# CircoController.net
KiCad netlist of a schematic drawn in EAGLE
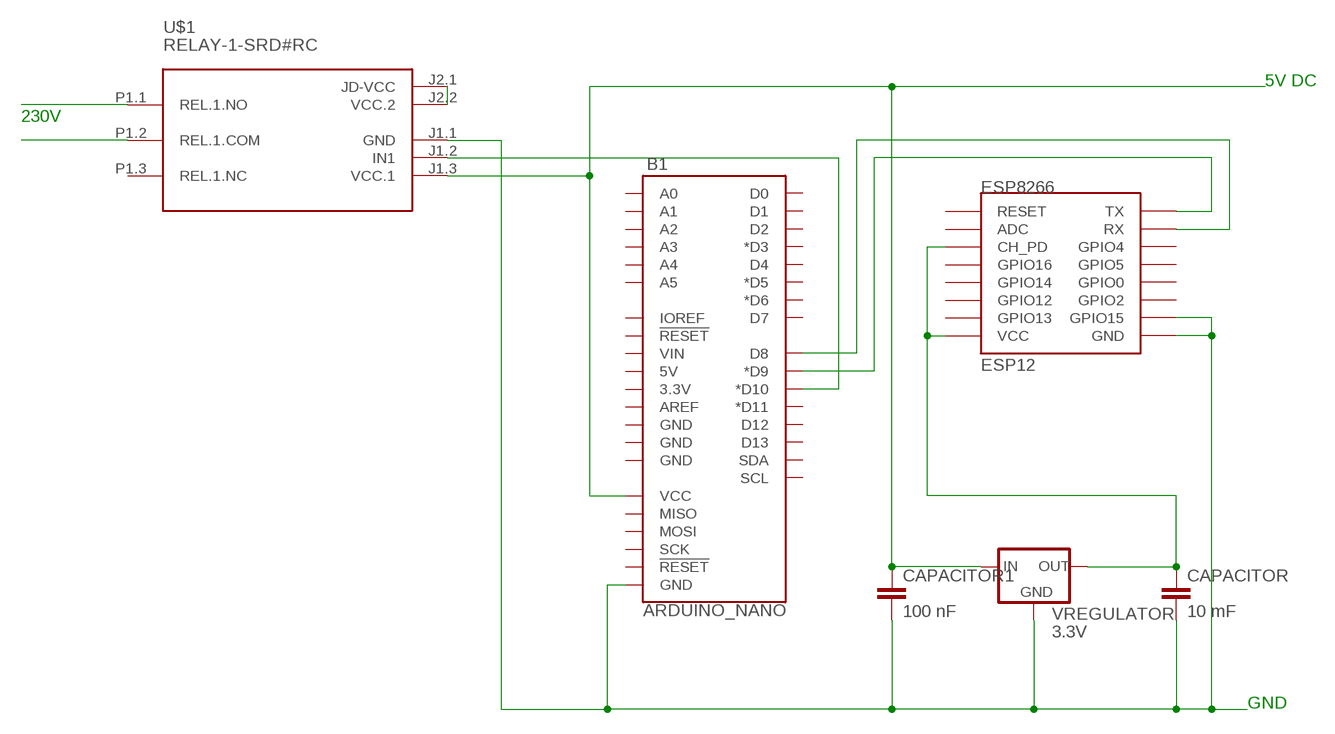
[diagram p0: schematic, sheet 1]

(export (version "E")
  (design (tool "Eeschema 10.0.6"))
  (components
    (comp (ref "B1")
      (value "ARDUINO_NANO")
      (footprint "eagle-import:ARDUINO_R3")
      (libsource (lib "eagle-import") (part "ARDUINO_UNO_R3"))
    )
    (comp (ref "CAPACITOR")
      (value "10 mF")
      (footprint "eagle-import:RESC0201_L")
      (libsource (lib "eagle-import") (part "CAPACITOR_0201_L"))
    )
    (comp (ref "CAPACITOR1")
      (value "100 nF")
      (footprint "eagle-import:RESC0201_L")
      (libsource (lib "eagle-import") (part "CAPACITOR_0201_L"))
    )
    (comp (ref "ESP8266")
      (value "ESP12")
      (footprint "eagle-import:ESP12")
      (libsource (lib "eagle-import") (part "ESP12"))
    )
    (comp (ref "U$1")
      (value "RELAY-1-SRD#RC")
      (footprint "eagle-import:RELAY-1-SRD#RC")
      (libsource (lib "eagle-import") (part "RELAY-1-SRD#RC"))
    )
    (comp (ref "VREGULATOR")
      (value "3.3V")
      (footprint "eagle-import:78LXX")
      (libsource (lib "eagle-import") (part "78LXX"))
    )
  )
  (nets
    (net (code "1") (name "Net-(B1-*D9)") (class "Default")
      (node (ref "B1") (pin "D9") (pinfunction "*D9_D9") (pintype "bidirectional"))
      (node (ref "ESP8266") (pin "TX") (pinfunction "TX_TX") (pintype "bidirectional"))
    )
    (net (code "2") (name "Net-(B1-*D10)") (class "Default")
      (node (ref "B1") (pin "D10") (pinfunction "*D10_D10") (pintype "bidirectional"))
      (node (ref "U$1") (pin "J1.2") (pinfunction "IN1_J1.2") (pintype "bidirectional"))
    )
    (net (code "3") (name "Net-(B1-PadD8)") (class "Default")
      (node (ref "B1") (pin "D8") (pinfunction "D8_D8") (pintype "bidirectional"))
      (node (ref "ESP8266") (pin "RX") (pinfunction "RX_RX") (pintype "bidirectional"))
    )
    (net (code "4") (name "Net-(CAPACITOR-Pad1)") (class "Default")
      (node (ref "CAPACITOR") (pin "1") (pinfunction "1_1") (pintype "passive"))
      (node (ref "ESP8266") (pin "CH_PD") (pinfunction "CH_PD_CH_PD") (pintype "bidirectional"))
      (node (ref "ESP8266") (pin "VCC") (pinfunction "VCC_VCC") (pintype "bidirectional"))
      (node (ref "VREGULATOR") (pin "OUT") (pinfunction "OUT_OUT") (pintype "passive"))
    )
    (net (code "5") (name "Net-(U$1-GND)") (class "Default")
      (node (ref "B1") (pin "GND@1") (pinfunction "GND_GND@1") (pintype "bidirectional"))
      (node (ref "CAPACITOR") (pin "2") (pinfunction "2_2") (pintype "passive"))
      (node (ref "CAPACITOR1") (pin "2") (pinfunction "2_2") (pintype "passive"))
      (node (ref "ESP8266") (pin "GND") (pinfunction "GND_GND") (pintype "bidirectional"))
      (node (ref "ESP8266") (pin "GPIO15") (pinfunction "GPIO15_GPIO15") (pintype "bidirectional"))
      (node (ref "U$1") (pin "J1.1") (pinfunction "GND_J1.1") (pintype "power_in"))
      (node (ref "VREGULATOR") (pin "GND") (pinfunction "GND_GND") (pintype "input"))
    )
    (net (code "6") (name "Net-(U$1-JD-VCC)") (class "Default")
      (node (ref "U$1") (pin "J2.1") (pinfunction "JD-VCC_J2.1") (pintype "bidirectional"))
      (node (ref "U$1") (pin "J2.2") (pinfunction "VCC.2_J2.2") (pintype "power_in"))
    )
    (net (code "7") (name "Net-(U$1-VCC.1)") (class "Default")
      (node (ref "B1") (pin "VCC") (pinfunction "VCC_VCC") (pintype "bidirectional"))
      (node (ref "CAPACITOR1") (pin "1") (pinfunction "1_1") (pintype "passive"))
      (node (ref "U$1") (pin "J1.3") (pinfunction "VCC.1_J1.3") (pintype "power_in"))
      (node (ref "VREGULATOR") (pin "IN") (pinfunction "IN_IN") (pintype "input"))
    )
    (net (code "8") (name "unconnected-(B1-*D3-PadD3)") (class "Default")
      (node (ref "B1") (pin "D3") (pinfunction "*D3_D3") (pintype "bidirectional"))
    )
    (net (code "9") (name "unconnected-(B1-*D5-PadD5)") (class "Default")
      (node (ref "B1") (pin "D5") (pinfunction "*D5_D5") (pintype "bidirectional"))
    )
    (net (code "10") (name "unconnected-(B1-*D6-PadD6)") (class "Default")
      (node (ref "B1") (pin "D6") (pinfunction "*D6_D6") (pintype "bidirectional"))
    )
    (net (code "11") (name "unconnected-(B1-*D11-PadD11)") (class "Default")
      (node (ref "B1") (pin "D11") (pinfunction "*D11_D11") (pintype "bidirectional"))
    )
    (net (code "12") (name "unconnected-(B1-GND-PadGND@2)") (class "Default")
      (node (ref "B1") (pin "GND@2") (pinfunction "GND_GND@2") (pintype "bidirectional"))
    )
    (net (code "13") (name "unconnected-(B1-GND-PadGND@3)") (class "Default")
      (node (ref "B1") (pin "GND@3") (pinfunction "GND_GND@3") (pintype "bidirectional"))
    )
    (net (code "14") (name "unconnected-(B1-GND-PadGND@4)") (class "Default")
      (node (ref "B1") (pin "GND@4") (pinfunction "GND_GND@4") (pintype "bidirectional"))
    )
    (net (code "15") (name "unconnected-(B1-Pad3.3V)") (class "Default")
      (node (ref "B1") (pin "3.3V") (pinfunction "3.3V_3.3V") (pintype "bidirectional"))
    )
    (net (code "16") (name "unconnected-(B1-Pad5V)") (class "Default")
      (node (ref "B1") (pin "5V") (pinfunction "5V_5V") (pintype "bidirectional"))
    )
    (net (code "17") (name "unconnected-(B1-PadA0)") (class "Default")
      (node (ref "B1") (pin "A0") (pinfunction "A0_A0") (pintype "bidirectional"))
    )
    (net (code "18") (name "unconnected-(B1-PadA1)") (class "Default")
      (node (ref "B1") (pin "A1") (pinfunction "A1_A1") (pintype "bidirectional"))
    )
    (net (code "19") (name "unconnected-(B1-PadA2)") (class "Default")
      (node (ref "B1") (pin "A2") (pinfunction "A2_A2") (pintype "bidirectional"))
    )
    (net (code "20") (name "unconnected-(B1-PadA3)") (class "Default")
      (node (ref "B1") (pin "A3") (pinfunction "A3_A3") (pintype "bidirectional"))
    )
    (net (code "21") (name "unconnected-(B1-PadA4)") (class "Default")
      (node (ref "B1") (pin "A4") (pinfunction "A4_A4") (pintype "bidirectional"))
    )
    (net (code "22") (name "unconnected-(B1-PadA5)") (class "Default")
      (node (ref "B1") (pin "A5") (pinfunction "A5_A5") (pintype "bidirectional"))
    )
    (net (code "23") (name "unconnected-(B1-PadAREF)") (class "Default")
      (node (ref "B1") (pin "AREF") (pinfunction "AREF_AREF") (pintype "bidirectional"))
    )
    (net (code "24") (name "unconnected-(B1-PadD0)") (class "Default")
      (node (ref "B1") (pin "D0") (pinfunction "D0_D0") (pintype "bidirectional"))
    )
    (net (code "25") (name "unconnected-(B1-PadD1)") (class "Default")
      (node (ref "B1") (pin "D1") (pinfunction "D1_D1") (pintype "bidirectional"))
    )
    (net (code "26") (name "unconnected-(B1-PadD2)") (class "Default")
      (node (ref "B1") (pin "D2") (pinfunction "D2_D2") (pintype "bidirectional"))
    )
    (net (code "27") (name "unconnected-(B1-PadD4)") (class "Default")
      (node (ref "B1") (pin "D4") (pinfunction "D4_D4") (pintype "bidirectional"))
    )
    (net (code "28") (name "unconnected-(B1-PadD7)") (class "Default")
      (node (ref "B1") (pin "D7") (pinfunction "D7_D7") (pintype "bidirectional"))
    )
    (net (code "29") (name "unconnected-(B1-PadD12)") (class "Default")
      (node (ref "B1") (pin "D12") (pinfunction "D12_D12") (pintype "bidirectional"))
    )
    (net (code "30") (name "unconnected-(B1-PadD13)") (class "Default")
      (node (ref "B1") (pin "D13") (pinfunction "D13_D13") (pintype "bidirectional"))
    )
    (net (code "31") (name "unconnected-(B1-PadIOREF)") (class "Default")
      (node (ref "B1") (pin "IOREF") (pinfunction "IOREF_IOREF") (pintype "bidirectional"))
    )
    (net (code "32") (name "unconnected-(B1-PadMISO)") (class "Default")
      (node (ref "B1") (pin "MISO") (pinfunction "MISO_MISO") (pintype "bidirectional"))
    )
    (net (code "33") (name "unconnected-(B1-PadMOSI)") (class "Default")
      (node (ref "B1") (pin "MOSI") (pinfunction "MOSI_MOSI") (pintype "bidirectional"))
    )
    (net (code "34") (name "unconnected-(B1-PadSCK)") (class "Default")
      (node (ref "B1") (pin "SCK") (pinfunction "SCK_SCK") (pintype "bidirectional"))
    )
    (net (code "35") (name "unconnected-(B1-PadSCL)") (class "Default")
      (node (ref "B1") (pin "SCL") (pinfunction "SCL_SCL") (pintype "bidirectional"))
    )
    (net (code "36") (name "unconnected-(B1-PadSDA)") (class "Default")
      (node (ref "B1") (pin "SDA") (pinfunction "SDA_SDA") (pintype "bidirectional"))
    )
    (net (code "37") (name "unconnected-(B1-PadVIN)") (class "Default")
      (node (ref "B1") (pin "VIN") (pinfunction "VIN_VIN") (pintype "bidirectional"))
    )
    (net (code "38") (name "unconnected-(B1-~{RESET}-PadRESET@1)") (class "Default")
      (node (ref "B1") (pin "RESET@1") (pinfunction "~{RESET}_RESET@1") (pintype "bidirectional"))
    )
    (net (code "39") (name "unconnected-(B1-~{RESET}-PadRESET@2)") (class "Default")
      (node (ref "B1") (pin "RESET@2") (pinfunction "~{RESET}_RESET@2") (pintype "bidirectional"))
    )
    (net (code "40") (name "unconnected-(ESP8266-PadADC)") (class "Default")
      (node (ref "ESP8266") (pin "ADC") (pinfunction "ADC_ADC") (pintype "bidirectional"))
    )
    (net (code "41") (name "unconnected-(ESP8266-PadGPIO0)") (class "Default")
      (node (ref "ESP8266") (pin "GPIO0") (pinfunction "GPIO0_GPIO0") (pintype "bidirectional"))
    )
    (net (code "42") (name "unconnected-(ESP8266-PadGPIO2)") (class "Default")
      (node (ref "ESP8266") (pin "GPIO2") (pinfunction "GPIO2_GPIO2") (pintype "bidirectional"))
    )
    (net (code "43") (name "unconnected-(ESP8266-PadGPIO4)") (class "Default")
      (node (ref "ESP8266") (pin "GPIO4") (pinfunction "GPIO4_GPIO4") (pintype "bidirectional"))
    )
    (net (code "44") (name "unconnected-(ESP8266-PadGPIO5)") (class "Default")
      (node (ref "ESP8266") (pin "GPIO5") (pinfunction "GPIO5_GPIO5") (pintype "bidirectional"))
    )
    (net (code "45") (name "unconnected-(ESP8266-PadGPIO12)") (class "Default")
      (node (ref "ESP8266") (pin "GPIO12") (pinfunction "GPIO12_GPIO12") (pintype "bidirectional"))
    )
    (net (code "46") (name "unconnected-(ESP8266-PadGPIO13)") (class "Default")
      (node (ref "ESP8266") (pin "GPIO13") (pinfunction "GPIO13_GPIO13") (pintype "bidirectional"))
    )
    (net (code "47") (name "unconnected-(ESP8266-PadGPIO14)") (class "Default")
      (node (ref "ESP8266") (pin "GPIO14") (pinfunction "GPIO14_GPIO14") (pintype "bidirectional"))
    )
    (net (code "48") (name "unconnected-(ESP8266-PadGPIO16)") (class "Default")
      (node (ref "ESP8266") (pin "GPIO16") (pinfunction "GPIO16_GPIO16") (pintype "bidirectional"))
    )
    (net (code "49") (name "unconnected-(ESP8266-PadRESET)") (class "Default")
      (node (ref "ESP8266") (pin "RESET") (pinfunction "RESET_RESET") (pintype "bidirectional"))
    )
    (net (code "50") (name "unconnected-(U$1-REL.1.COM-PadP1.2)") (class "Default")
      (node (ref "U$1") (pin "P1.2") (pinfunction "REL.1.COM_P1.2") (pintype "bidirectional"))
    )
    (net (code "51") (name "unconnected-(U$1-REL.1.NC-PadP1.3)") (class "Default")
      (node (ref "U$1") (pin "P1.3") (pinfunction "REL.1.NC_P1.3") (pintype "bidirectional"))
    )
    (net (code "52") (name "unconnected-(U$1-REL.1.NO-PadP1.1)") (class "Default")
      (node (ref "U$1") (pin "P1.1") (pinfunction "REL.1.NO_P1.1") (pintype "bidirectional"))
    )
  )
)
